# display_board.net
KiCad netlist of a schematic drawn in EAGLE
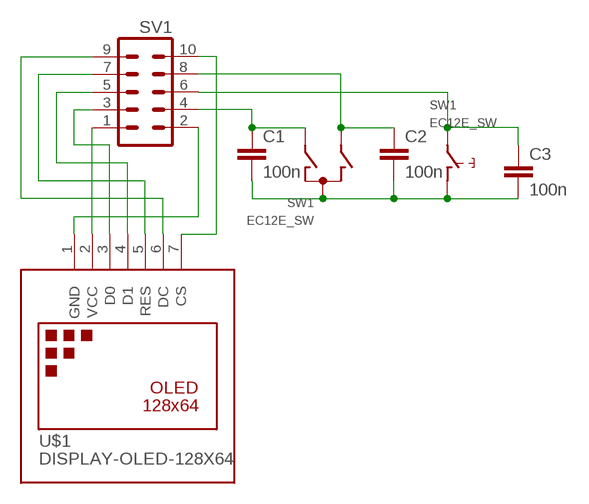
[diagram p0: schematic, sheet 1]

(export (version "E")
  (design (tool "Eeschema 10.0.6"))
  (components
    (comp (ref "C1")
      (value "100n")
      (footprint "eagle-import:C1206")
      (libsource (lib "eagle-import") (part "C-EUC1206"))
    )
    (comp (ref "C2")
      (value "100n")
      (footprint "eagle-import:C1206")
      (libsource (lib "eagle-import") (part "C-EUC1206"))
    )
    (comp (ref "C3")
      (value "100n")
      (footprint "eagle-import:C1206")
      (libsource (lib "eagle-import") (part "C-EUC1206"))
    )
    (comp (ref "SV1")
      (value "MA05-2")
      (footprint "eagle-import:MA05-2")
      (libsource (lib "eagle-import") (part "MA05-2"))
    )
    (comp (ref "SW1")
      (value "EC12E_SW")
      (footprint "eagle-import:ALPS_EC12E_SW")
      (fields (field (name "MPN") "EC12E2424407"))
      (libsource (lib "eagle-import") (part "EC12E_SW"))
    )
    (comp (ref "U$1")
      (value "DISPLAY-OLED-128X64")
      (footprint "eagle-import:DISPLAY-OLED-128X64")
      (libsource (lib "eagle-import") (part "DISPLAY-OLED-128X64"))
    )
  )
  (nets
    (net (code "1") (name "Net-(C1-Pad1)") (class "Default")
      (node (ref "C1") (pin "1") (pinfunction "1_1") (pintype "passive"))
      (node (ref "SV1") (pin "4") (pinfunction "4_4") (pintype "passive"))
      (node (ref "SW1") (pin "A") (pinfunction "A_A") (pintype "passive"))
    )
    (net (code "2") (name "Net-(C2-Pad1)") (class "Default")
      (node (ref "C2") (pin "1") (pinfunction "1_1") (pintype "passive"))
      (node (ref "SV1") (pin "8") (pinfunction "8_8") (pintype "passive"))
      (node (ref "SW1") (pin "B") (pinfunction "B_B") (pintype "passive"))
    )
    (net (code "3") (name "Net-(SW1B-1)") (class "Default")
      (node (ref "C1") (pin "2") (pinfunction "2_2") (pintype "passive"))
      (node (ref "C2") (pin "2") (pinfunction "2_2") (pintype "passive"))
      (node (ref "C3") (pin "2") (pinfunction "2_2") (pintype "passive"))
      (node (ref "SW1") (pin "C") (pinfunction "C_C") (pintype "passive"))
      (node (ref "SW1") (pin "D") (pinfunction "1_D") (pintype "passive"))
    )
    (net (code "4") (name "Net-(SW1B-2)") (class "Default")
      (node (ref "C3") (pin "1") (pinfunction "1_1") (pintype "passive"))
      (node (ref "SV1") (pin "6") (pinfunction "6_6") (pintype "passive"))
      (node (ref "SW1") (pin "E") (pinfunction "2_E") (pintype "passive"))
    )
    (net (code "5") (name "Net-(U$1-CS)") (class "Default")
      (node (ref "SV1") (pin "10") (pinfunction "10_10") (pintype "passive"))
      (node (ref "U$1") (pin "7") (pinfunction "CS_7") (pintype "bidirectional"))
    )
    (net (code "6") (name "Net-(U$1-D0)") (class "Default")
      (node (ref "SV1") (pin "3") (pinfunction "3_3") (pintype "passive"))
      (node (ref "U$1") (pin "3") (pinfunction "D0_3") (pintype "bidirectional"))
    )
    (net (code "7") (name "Net-(U$1-D1)") (class "Default")
      (node (ref "SV1") (pin "5") (pinfunction "5_5") (pintype "passive"))
      (node (ref "U$1") (pin "4") (pinfunction "D1_4") (pintype "bidirectional"))
    )
    (net (code "8") (name "Net-(U$1-DC)") (class "Default")
      (node (ref "SV1") (pin "9") (pinfunction "9_9") (pintype "passive"))
      (node (ref "U$1") (pin "6") (pinfunction "DC_6") (pintype "bidirectional"))
    )
    (net (code "9") (name "Net-(U$1-GND)") (class "Default")
      (node (ref "SV1") (pin "2") (pinfunction "2_2") (pintype "passive"))
      (node (ref "U$1") (pin "1") (pinfunction "GND_1") (pintype "power_in"))
    )
    (net (code "10") (name "Net-(U$1-RES)") (class "Default")
      (node (ref "SV1") (pin "7") (pinfunction "7_7") (pintype "passive"))
      (node (ref "U$1") (pin "5") (pinfunction "RES_5") (pintype "bidirectional"))
    )
    (net (code "11") (name "Net-(U$1-VCC)") (class "Default")
      (node (ref "SV1") (pin "1") (pinfunction "1_1") (pintype "passive"))
      (node (ref "U$1") (pin "2") (pinfunction "VCC_2") (pintype "power_in"))
    )
  )
)
